# CAN.net
KiCad netlist of a schematic drawn in Altium Designer
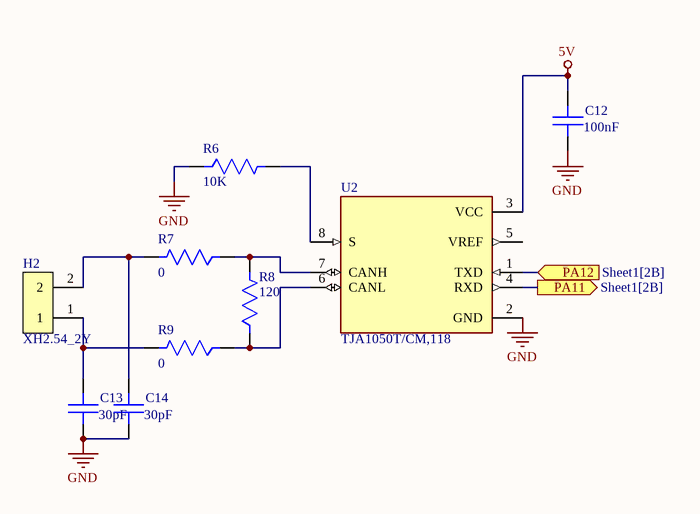
[diagram p0: CAN.SchDoc]

(export (version "E")
  (design (tool "Eeschema 10.0.6"))
  (components
    (comp (ref "C12")
      (value "100nF")
      (footprint "C0603")
      (libsource (lib "Tram_muoi_VietAn") (part "Capacitor 0603"))
    )
    (comp (ref "C13")
      (value "30pF")
      (footprint "C0603")
      (libsource (lib "Tram_muoi_VietAn") (part "Capacitor 0603"))
    )
    (comp (ref "C14")
      (value "30pF")
      (footprint "C0603")
      (libsource (lib "Tram_muoi_VietAn") (part "Capacitor 0603"))
    )
    (comp (ref "H2")
      (value "XH2.54_2Y")
      (footprint "JST-XH-02-PACKAGE-LONG-PAD")
      (libsource (lib "IoTVision_Library") (part "XH2.54_2Y"))
    )
    (comp (ref "R6")
      (value "10K")
      (footprint "R0603")
      (description "SMD Resistor 0603")
      (fields
        (field (name "MANUFACTURER") "Yageo")
        (field (name "MANUFACTURER PART NUMBER") "RC0603FR-071KL")
      )
      (libsource (lib "Tram_muoi_VietAn") (part "Resistor 0603"))
    )
    (comp (ref "R7")
      (value "0")
      (footprint "R0603")
      (description "SMD Resistor 0603")
      (fields
        (field (name "MANUFACTURER") "Yageo")
        (field (name "MANUFACTURER PART NUMBER") "RC0603FR-071KL")
      )
      (libsource (lib "Tram_muoi_VietAn") (part "Resistor 0603"))
    )
    (comp (ref "R8")
      (value "120")
      (footprint "R0603")
      (description "SMD Resistor 0603")
      (fields
        (field (name "MANUFACTURER") "Yageo")
        (field (name "MANUFACTURER PART NUMBER") "RC0603FR-071KL")
      )
      (libsource (lib "Tram_muoi_VietAn") (part "Resistor 0603"))
    )
    (comp (ref "R9")
      (value "0")
      (footprint "R0603")
      (description "SMD Resistor 0603")
      (fields
        (field (name "MANUFACTURER") "Yageo")
        (field (name "MANUFACTURER PART NUMBER") "RC0603FR-071KL")
      )
      (libsource (lib "Tram_muoi_VietAn") (part "Resistor 0603"))
    )
    (comp (ref "U2")
      (value "TJA1050T/CM,118")
      (footprint "SOIC127P600X175-8N")
      (description "1/1 Transceiver Half CANbus 8-SO")
      (fields (field (name "MF") "NXP USA"))
      (libsource (lib "TJA1050T_CM_118") (part "TJA1050T/CM,118"))
    )
  )
  (nets
    (net (code "1") (name "/PA11") (class "Default")
      (node (ref "U2") (pin "4") (pinfunction "RXD_4") (pintype "output"))
    )
    (net (code "2") (name "/PA12") (class "Default")
      (node (ref "U2") (pin "1") (pinfunction "TXD_1") (pintype "input"))
    )
    (net (code "3") (name "5V") (class "Default")
      (node (ref "C12") (pin "1") (pinfunction "1_1") (pintype "passive"))
      (node (ref "U2") (pin "3") (pinfunction "VCC_3") (pintype "power_in"))
    )
    (net (code "4") (name "GND") (class "Default")
      (node (ref "C12") (pin "2") (pinfunction "2_2") (pintype "passive"))
      (node (ref "C13") (pin "2") (pinfunction "2_2") (pintype "passive"))
      (node (ref "C14") (pin "2") (pinfunction "2_2") (pintype "passive"))
      (node (ref "R6") (pin "1") (pinfunction "1_1") (pintype "passive"))
      (node (ref "U2") (pin "2") (pinfunction "GND_2") (pintype "power_in"))
    )
    (net (code "5") (name "Net-(C13-Pad1)") (class "Default")
      (node (ref "C13") (pin "1") (pinfunction "1_1") (pintype "passive"))
      (node (ref "H2") (pin "1") (pinfunction "1_1") (pintype "passive"))
      (node (ref "R9") (pin "2") (pinfunction "2_2") (pintype "passive"))
    )
    (net (code "6") (name "Net-(C14-Pad1)") (class "Default")
      (node (ref "C14") (pin "1") (pinfunction "1_1") (pintype "passive"))
      (node (ref "H2") (pin "2") (pinfunction "2_2") (pintype "passive"))
      (node (ref "R7") (pin "2") (pinfunction "2_2") (pintype "passive"))
    )
    (net (code "7") (name "Net-(U2-CANH)") (class "Default")
      (node (ref "R7") (pin "1") (pinfunction "1_1") (pintype "passive"))
      (node (ref "R8") (pin "2") (pinfunction "2_2") (pintype "passive"))
      (node (ref "U2") (pin "7") (pinfunction "CANH_7") (pintype "bidirectional"))
    )
    (net (code "8") (name "Net-(U2-CANL)") (class "Default")
      (node (ref "R8") (pin "1") (pinfunction "1_1") (pintype "passive"))
      (node (ref "R9") (pin "1") (pinfunction "1_1") (pintype "passive"))
      (node (ref "U2") (pin "6") (pinfunction "CANL_6") (pintype "bidirectional"))
    )
    (net (code "9") (name "Net-(U2-S)") (class "Default")
      (node (ref "R6") (pin "2") (pinfunction "2_2") (pintype "passive"))
      (node (ref "U2") (pin "8") (pinfunction "S_8") (pintype "input"))
    )
    (net (code "10") (name "unconnected-(U2-VREF-Pad5)") (class "Default")
      (node (ref "U2") (pin "5") (pinfunction "VREF_5") (pintype "output"))
    )
  )
)
